# Supply_VCO.net
KiCad netlist of a schematic drawn in Altium Designer
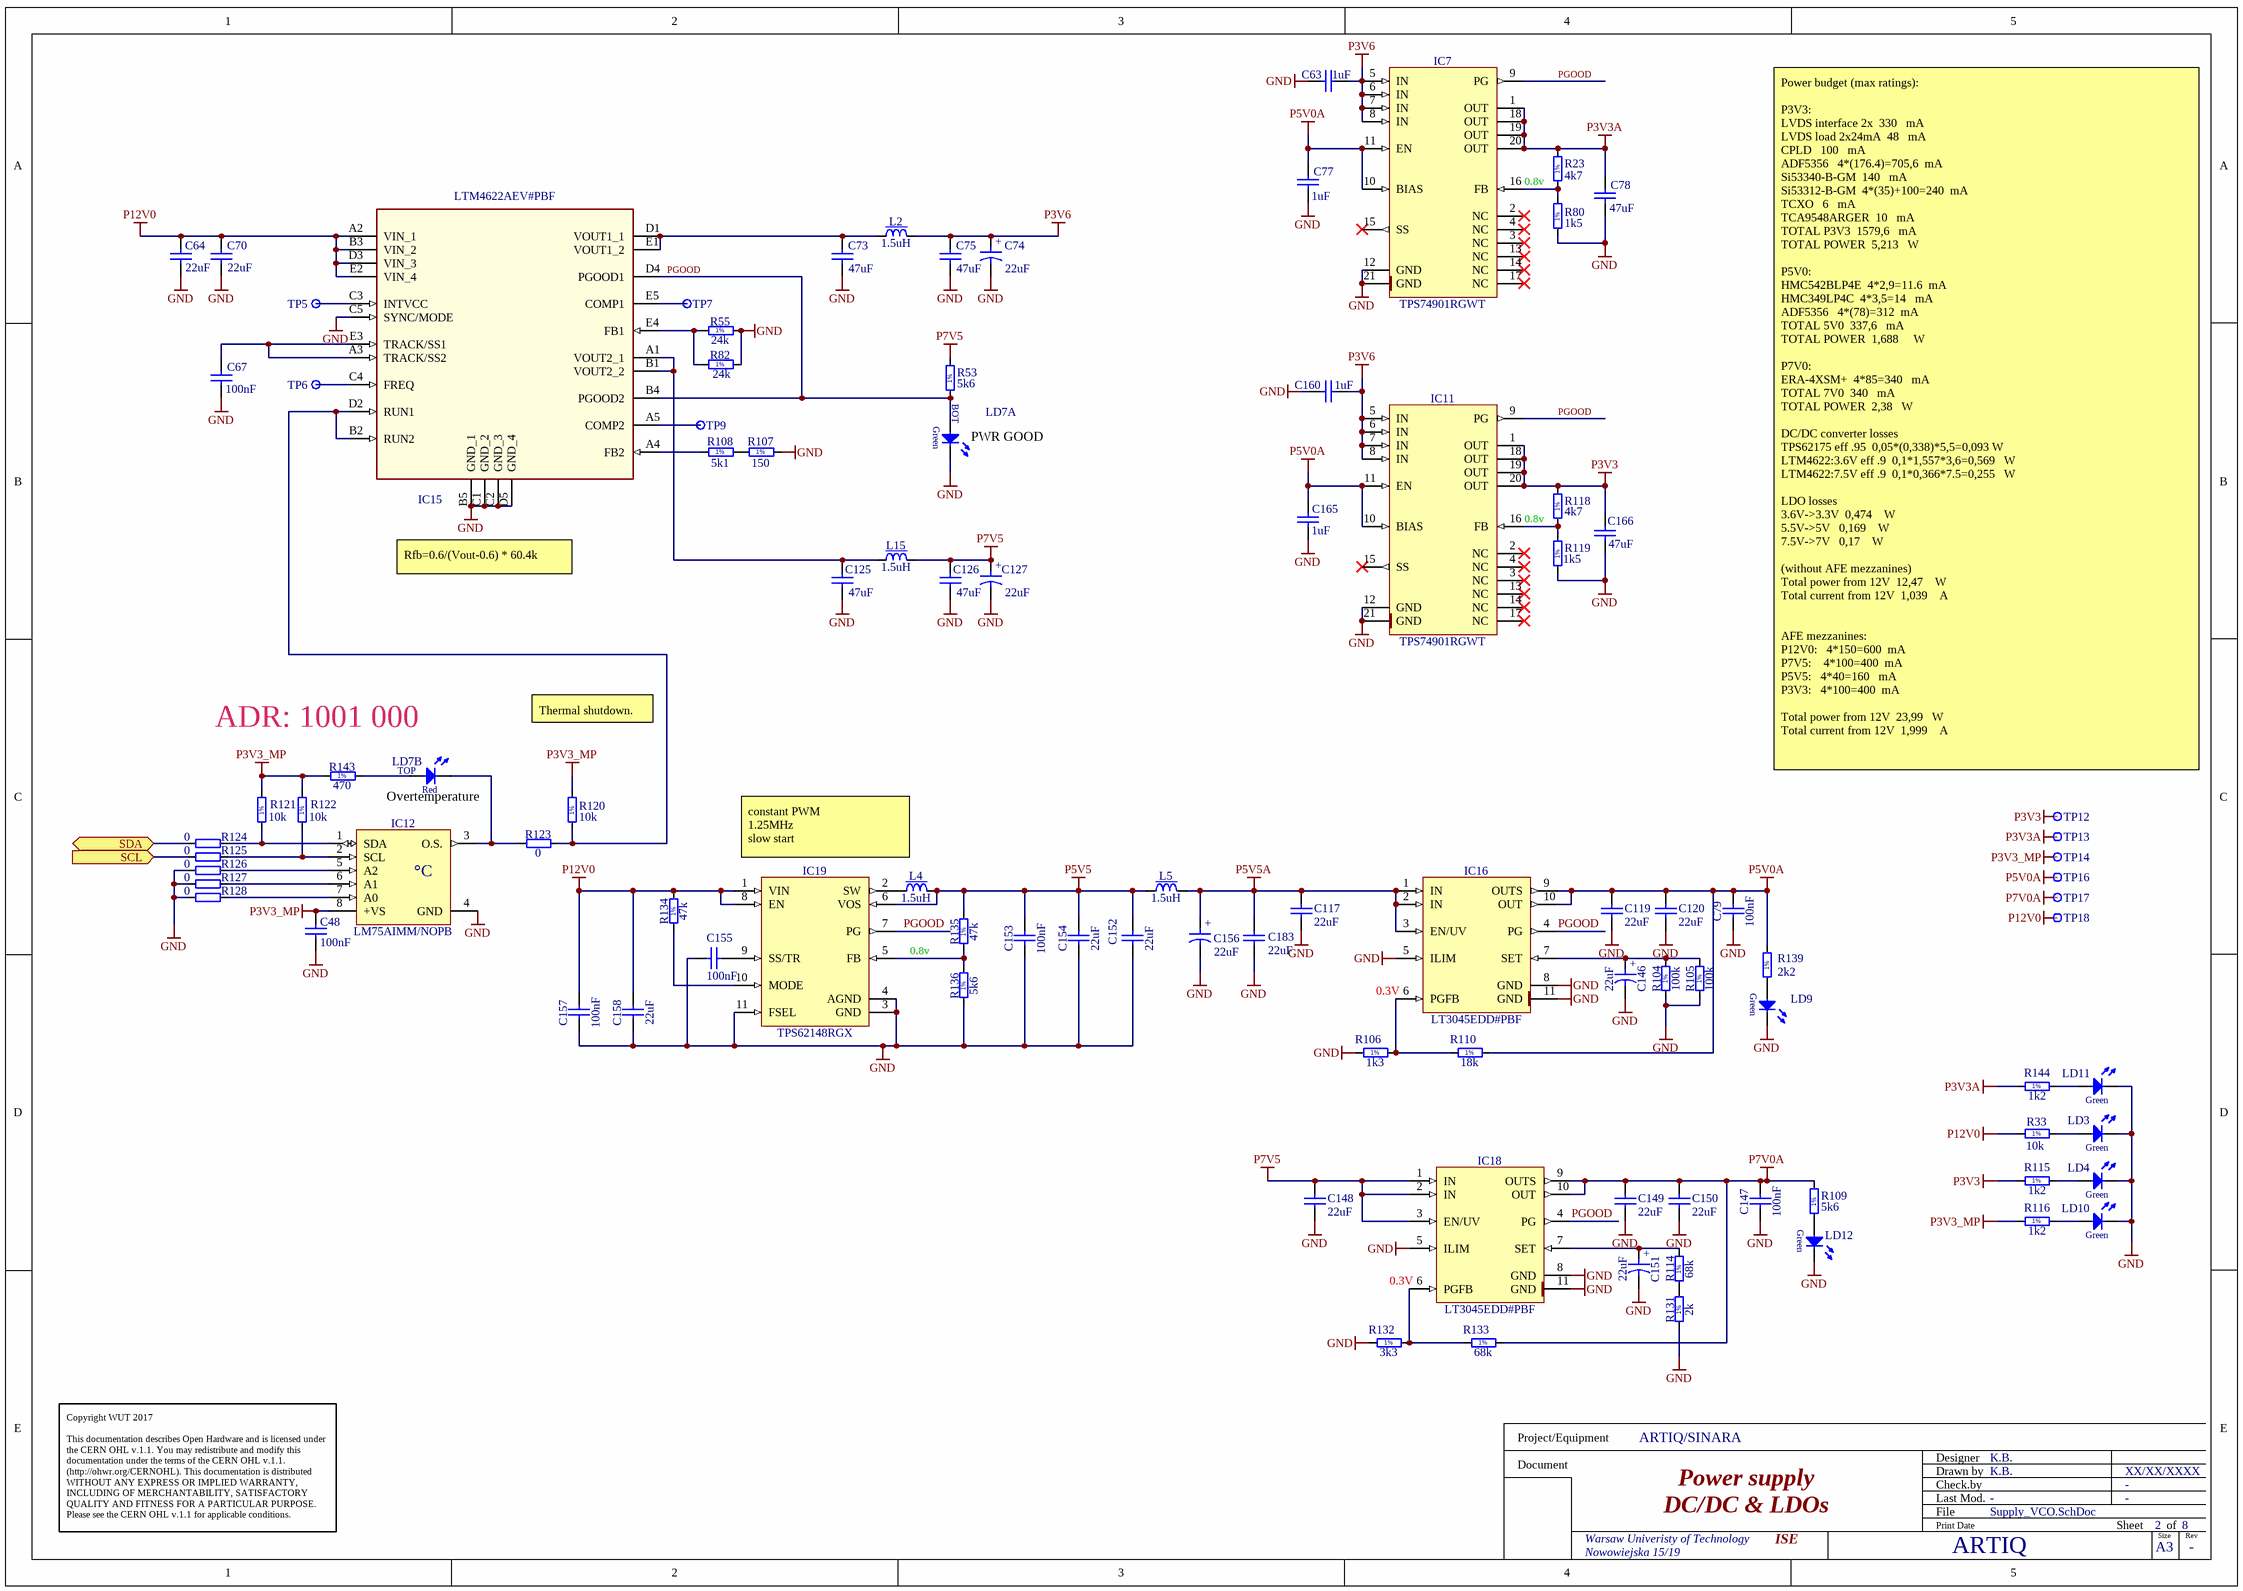
[diagram p0: Supply_VCO.SchDoc]

(export (version "E")
  (design (tool "Eeschema 10.0.6"))
  (components
    (comp (ref "C48")
      (value "100nF")
      (footprint "CAPC1005X55N")
      (description "Non-polarised capacitor")
      (fields (field (name "PART NUMBER") "CC0402_100NF_16V_10%_X5R") (field (name "VOLTAGE") "16V"))
      (libsource (lib "Capacitors") (part "Capacitor - non polarized"))
    )
    (comp (ref "C63")
      (value "1uF")
      (footprint "CAPC1005X55N")
      (description "Non-polarised capacitor")
      (fields (field (name "PART NUMBER") "CC0402_1UF_16V_10%_X5R") (field (name "VOLTAGE") "16V"))
      (libsource (lib "Capacitors") (part "Capacitor - non polarized"))
    )
    (comp (ref "C64")
      (value "22uF")
      (footprint "CAPC2012X135N")
      (description "Non-polarised capacitor")
      (fields (field (name "PART NUMBER") "CC0805_22UF_16V_10%_X5R") (field (name "VOLTAGE") "16V"))
      (libsource (lib "Capacitors") (part "Capacitor - non polarized"))
    )
    (comp (ref "C67")
      (value "100nF")
      (footprint "CAPC1005X55N")
      (description "Non-polarised capacitor")
      (fields (field (name "PART NUMBER") "CC0402_100NF_16V_10%_X5R") (field (name "VOLTAGE") "16V"))
      (libsource (lib "Capacitors") (part "Capacitor - non polarized"))
    )
    (comp (ref "C70")
      (value "22uF")
      (footprint "CAPC2012X135N")
      (description "Non-polarised capacitor")
      (fields (field (name "PART NUMBER") "CC0805_22UF_16V_10%_X5R") (field (name "VOLTAGE") "16V"))
      (libsource (lib "Capacitors") (part "Capacitor - non polarized"))
    )
    (comp (ref "C73")
      (value "47uF")
      (footprint "CAPC3225X270N")
      (description "Non-polarised capacitor")
      (fields (field (name "PART NUMBER") "CC1210_47UF_10V_20%_X5R") (field (name "VOLTAGE") "10V"))
      (libsource (lib "Capacitors") (part "Capacitor - non polarized"))
    )
    (comp (ref "C74")
      (value "22uF")
      (footprint "CAPMP3528X210N")
      (description "Polarised capacitor")
      (fields (field (name "PART NUMBER") "CTE3528-21_22UF_10V_10%_LESR0700") (field (name "VOLTAGE") "10V"))
      (libsource (lib "Capacitors") (part "Capacitor - polarized"))
    )
    (comp (ref "C75")
      (value "47uF")
      (footprint "CAPC3225X270N")
      (description "Non-polarised capacitor")
      (fields (field (name "PART NUMBER") "CC1210_47UF_10V_20%_X5R") (field (name "VOLTAGE") "10V"))
      (libsource (lib "Capacitors") (part "Capacitor - non polarized"))
    )
    (comp (ref "C77")
      (value "1uF")
      (footprint "CAPC1005X55N")
      (description "Non-polarised capacitor")
      (fields (field (name "PART NUMBER") "CC0402_1UF_16V_10%_X5R") (field (name "VOLTAGE") "16V"))
      (libsource (lib "Capacitors") (part "Capacitor - non polarized"))
    )
    (comp (ref "C78")
      (value "47uF")
      (footprint "CAPC3225X270N")
      (description "Non-polarised capacitor")
      (fields (field (name "PART NUMBER") "CC1210_47UF_10V_20%_X5R") (field (name "VOLTAGE") "10V"))
      (libsource (lib "Capacitors") (part "Capacitor - non polarized"))
    )
    (comp (ref "C79")
      (value "100nF")
      (footprint "CAPC1005X55N")
      (description "Non-polarised capacitor")
      (fields (field (name "PART NUMBER") "CC0402_100NF_16V_10%_X5R") (field (name "VOLTAGE") "16V"))
      (libsource (lib "Capacitors") (part "Capacitor - non polarized"))
    )
    (comp (ref "C117")
      (value "22uF")
      (footprint "CAPC2012X135N")
      (description "Non-polarised capacitor")
      (fields (field (name "PART NUMBER") "CC0805_22UF_16V_10%_X5R") (field (name "VOLTAGE") "16V"))
      (libsource (lib "Capacitors") (part "Capacitor - non polarized"))
    )
    (comp (ref "C119")
      (value "22uF")
      (footprint "CAPC2012X135N")
      (description "Non-polarised capacitor")
      (fields (field (name "PART NUMBER") "CC0805_22UF_16V_10%_X5R") (field (name "VOLTAGE") "16V"))
      (libsource (lib "Capacitors") (part "Capacitor - non polarized"))
    )
    (comp (ref "C120")
      (value "22uF")
      (footprint "CAPC2012X135N")
      (description "Non-polarised capacitor")
      (fields (field (name "PART NUMBER") "CC0805_22UF_16V_10%_X5R") (field (name "VOLTAGE") "16V"))
      (libsource (lib "Capacitors") (part "Capacitor - non polarized"))
    )
    (comp (ref "C125")
      (value "47uF")
      (footprint "CAPC3225X270N")
      (description "Non-polarised capacitor")
      (fields (field (name "PART NUMBER") "CC1210_47UF_10V_20%_X5R") (field (name "VOLTAGE") "10V"))
      (libsource (lib "Capacitors") (part "Capacitor - non polarized"))
    )
    (comp (ref "C126")
      (value "47uF")
      (footprint "CAPC3225X270N")
      (description "Non-polarised capacitor")
      (fields (field (name "PART NUMBER") "CC1210_47UF_10V_20%_X5R") (field (name "VOLTAGE") "10V"))
      (libsource (lib "Capacitors") (part "Capacitor - non polarized"))
    )
    (comp (ref "C127")
      (value "22uF")
      (footprint "CAPMP3528X210N")
      (description "Polarised capacitor")
      (fields (field (name "PART NUMBER") "CTE3528-21_22UF_10V_10%_LESR0700") (field (name "VOLTAGE") "10V"))
      (libsource (lib "Capacitors") (part "Capacitor - polarized"))
    )
    (comp (ref "C146")
      (value "22uF")
      (footprint "CAPMP3528X210N")
      (description "Polarised capacitor")
      (fields (field (name "PART NUMBER") "CTE3528-21_22UF_10V_10%_LESR0700") (field (name "VOLTAGE") "10V"))
      (libsource (lib "Capacitors") (part "Capacitor - polarized"))
    )
    (comp (ref "C147")
      (value "100nF")
      (footprint "CAPC1005X55N")
      (description "Non-polarised capacitor")
      (fields (field (name "PART NUMBER") "CC0402_100NF_16V_10%_X5R") (field (name "VOLTAGE") "16V"))
      (libsource (lib "Capacitors") (part "Capacitor - non polarized"))
    )
    (comp (ref "C148")
      (value "22uF")
      (footprint "CAPC2012X135N")
      (description "Non-polarised capacitor")
      (fields (field (name "PART NUMBER") "CC0805_22UF_16V_10%_X5R") (field (name "VOLTAGE") "16V"))
      (libsource (lib "Capacitors") (part "Capacitor - non polarized"))
    )
    (comp (ref "C149")
      (value "22uF")
      (footprint "CAPC2012X135N")
      (description "Non-polarised capacitor")
      (fields (field (name "PART NUMBER") "CC0805_22UF_16V_10%_X5R") (field (name "VOLTAGE") "16V"))
      (libsource (lib "Capacitors") (part "Capacitor - non polarized"))
    )
    (comp (ref "C150")
      (value "22uF")
      (footprint "CAPC2012X135N")
      (description "Non-polarised capacitor")
      (fields (field (name "PART NUMBER") "CC0805_22UF_16V_10%_X5R") (field (name "VOLTAGE") "16V"))
      (libsource (lib "Capacitors") (part "Capacitor - non polarized"))
    )
    (comp (ref "C151")
      (value "22uF")
      (footprint "CAPMP3528X210N")
      (description "Polarised capacitor")
      (fields (field (name "PART NUMBER") "CTE3528-21_22UF_10V_10%_LESR0700") (field (name "VOLTAGE") "10V"))
      (libsource (lib "Capacitors") (part "Capacitor - polarized"))
    )
    (comp (ref "C152")
      (value "22uF")
      (footprint "CAPC2012X135N")
      (description "Non-polarised capacitor")
      (fields (field (name "PART NUMBER") "CC0805_22UF_16V_10%_X5R") (field (name "VOLTAGE") "16V"))
      (libsource (lib "Capacitors") (part "Capacitor - non polarized"))
    )
    (comp (ref "C153")
      (value "100nF")
      (footprint "CAPC1005X55N")
      (description "Non-polarised capacitor")
      (fields (field (name "PART NUMBER") "CC0402_100NF_16V_10%_X5R") (field (name "VOLTAGE") "16V"))
      (libsource (lib "Capacitors") (part "Capacitor - non polarized"))
    )
    (comp (ref "C154")
      (value "22uF")
      (footprint "CAPC2012X135N")
      (description "Non-polarised capacitor")
      (fields (field (name "PART NUMBER") "CC0805_22UF_16V_10%_X5R") (field (name "VOLTAGE") "16V"))
      (libsource (lib "Capacitors") (part "Capacitor - non polarized"))
    )
    (comp (ref "C155")
      (value "100nF")
      (footprint "CAPC1005X55N")
      (description "Non-polarised capacitor")
      (fields (field (name "PART NUMBER") "CC0402_100NF_16V_10%_X5R") (field (name "VOLTAGE") "16V"))
      (libsource (lib "Capacitors") (part "Capacitor - non polarized"))
    )
    (comp (ref "C156")
      (value "22uF")
      (footprint "CAPMP3528X210N")
      (description "Polarised capacitor")
      (fields (field (name "PART NUMBER") "CTE3528-21_22UF_10V_10%_LESR0700") (field (name "VOLTAGE") "10V"))
      (libsource (lib "Capacitors") (part "Capacitor - polarized"))
    )
    (comp (ref "C157")
      (value "100nF")
      (footprint "CAPC1005X55N")
      (description "Non-polarised capacitor")
      (fields (field (name "PART NUMBER") "CC0402_100NF_16V_10%_X5R") (field (name "VOLTAGE") "16V"))
      (libsource (lib "Capacitors") (part "Capacitor - non polarized"))
    )
    (comp (ref "C158")
      (value "22uF")
      (footprint "CAPC2012X135N")
      (description "Non-polarised capacitor")
      (fields (field (name "PART NUMBER") "CC0805_22UF_16V_10%_X5R") (field (name "VOLTAGE") "16V"))
      (libsource (lib "Capacitors") (part "Capacitor - non polarized"))
    )
    (comp (ref "C160")
      (value "1uF")
      (footprint "CAPC1005X55N")
      (description "Non-polarised capacitor")
      (fields (field (name "PART NUMBER") "CC0402_1UF_16V_10%_X5R") (field (name "VOLTAGE") "16V"))
      (libsource (lib "Capacitors") (part "Capacitor - non polarized"))
    )
    (comp (ref "C165")
      (value "1uF")
      (footprint "CAPC1005X55N")
      (description "Non-polarised capacitor")
      (fields (field (name "PART NUMBER") "CC0402_1UF_16V_10%_X5R") (field (name "VOLTAGE") "16V"))
      (libsource (lib "Capacitors") (part "Capacitor - non polarized"))
    )
    (comp (ref "C166")
      (value "47uF")
      (footprint "CAPC3225X270N")
      (description "Non-polarised capacitor")
      (fields (field (name "PART NUMBER") "CC1210_47UF_10V_20%_X5R") (field (name "VOLTAGE") "10V"))
      (libsource (lib "Capacitors") (part "Capacitor - non polarized"))
    )
    (comp (ref "C183")
      (value "22uF")
      (footprint "CAPC2012X135N")
      (description "Non-polarised capacitor")
      (fields (field (name "PART NUMBER") "CC0805_22UF_16V_10%_X5R") (field (name "VOLTAGE") "16V"))
      (libsource (lib "Capacitors") (part "Capacitor - non polarized"))
    )
    (comp (ref "IC7")
      (value "TPS74901RGWT")
      (footprint "QFN65P500X500X100-21N-S325")
      (description "3A, 0.8 to 3.6V Adjustable Low-Dropout Linear Regulator with Programmable Soft-Start")
      (fields (field (name "MANUFACTURER") "TEXAS INSTRUMENTS"))
      (libsource (lib "ICs And Semiconductors") (part "TPS74901RGWT"))
    )
    (comp (ref "IC11")
      (value "TPS74901RGWT")
      (footprint "QFN65P500X500X100-21N-S325")
      (description "3A, 0.8 to 3.6V Adjustable Low-Dropout Linear Regulator with Programmable Soft-Start")
      (fields (field (name "MANUFACTURER") "TEXAS INSTRUMENTS"))
      (libsource (lib "ICs And Semiconductors") (part "TPS74901RGWT"))
    )
    (comp (ref "IC12")
      (value "LM75AIMM/NOPB")
      (footprint "SOP65P490X109-8N")
      (description "Digital Temperature Sensor and Thermal Watchdog with Two-Wire Interface")
      (fields (field (name "MANUFACTURER") "TEXAS INSTRUMENTS"))
      (libsource (lib "ICs And Semiconductors") (part "LM75"))
    )
    (comp (ref "IC15")
      (value "LTM4622AEV#PBF")
      (footprint "LGA25C127P5X5_625X625X190")
      (description "Dual Ultrathin 2A or Single 4A, 3.6V to 20V, 1.5V to 12V   Step-Down DC/DC μModule Regulator")
      (fields (field (name "MANUFACTURER") "LINEAR TECHNOLOGY"))
      (libsource (lib "LIBRARY_SCH") (part "PM_LTM4622"))
    )
    (comp (ref "IC16")
      (value "LT3045EDD#PBF")
      (footprint "SON50P300X300X80-11N-R175X248")
      (description "20V, 500mA, Ultralow Noise, Ultrahigh PSRR Linear Regulator")
      (fields (field (name "MANUFACTURER") "LINEAR TECHNOLOGY"))
      (libsource (lib "ICs And Semiconductors") (part "LT3045EDD"))
    )
    (comp (ref "IC18")
      (value "LT3045EDD#PBF")
      (footprint "SON50P300X300X80-11N-R175X248")
      (description "20V, 500mA, Ultralow Noise, Ultrahigh PSRR Linear Regulator")
      (fields (field (name "MANUFACTURER") "LINEAR TECHNOLOGY"))
      (libsource (lib "ICs And Semiconductors") (part "LT3045EDD"))
    )
    (comp (ref "IC19")
      (value "TPS62148RGX")
      (footprint "TEXAS_RGX0011A")
      (description "3V-17V 2A Step-Down Converter, High Accuracy, With DCS-Control")
      (fields (field (name "MANUFACTURER") "TEXAS INSTRUMENTS"))
      (libsource (lib "ICs And Semiconductors") (part "TPS62148"))
    )
    (comp (ref "L2")
      (value "1.5uH")
      (footprint "IND_TDK_SPM6530")
      (description "Inductor With Core")
      (fields (field (name "PART NUMBER") "IND_1.5UH_20%_TDK_SPM6530") (field (name "POWER") "11A"))
      (libsource (lib "Inductors & Transformers") (part "Inductor With Magnetic core"))
    )
    (comp (ref "L4")
      (value "1.5uH")
      (footprint "IND_TDK_SPM6530")
      (description "Inductor With Core")
      (fields (field (name "PART NUMBER") "IND_1.5UH_20%_TDK_SPM6530") (field (name "POWER") "11A"))
      (libsource (lib "Inductors & Transformers") (part "Inductor With Magnetic core"))
    )
    (comp (ref "L5")
      (value "1.5uH")
      (footprint "IND_TDK_SPM6530")
      (description "Inductor With Core")
      (fields (field (name "PART NUMBER") "IND_1.5UH_20%_TDK_SPM6530") (field (name "POWER") "11A"))
      (libsource (lib "Inductors & Transformers") (part "Inductor With Magnetic core"))
    )
    (comp (ref "L15")
      (value "1.5uH")
      (footprint "IND_TDK_SPM6530")
      (description "Inductor With Core")
      (fields (field (name "PART NUMBER") "IND_1.5UH_20%_TDK_SPM6530") (field (name "POWER") "11A"))
      (libsource (lib "Inductors & Transformers") (part "Inductor With Magnetic core"))
    )
    (comp (ref "LD3")
      (value "Green")
      (footprint "LED_KINGBRIGHT_KPH-1608CGCKr")
      (description "Green 0603")
      (fields
        (field (name "PART NUMBER") "LED_KINGBRIGHT_KPH-1608CGCK")
        (field (name "MANUFACTURER") "KINGBRIGHT")
      )
      (libsource (lib "LIBRARY_SCH") (part "LED_0603_Green"))
    )
    (comp (ref "LD4")
      (value "Green")
      (footprint "LED_KINGBRIGHT_KPH-1608CGCKr")
      (description "Green 0603")
      (fields
        (field (name "PART NUMBER") "LED_KINGBRIGHT_KPH-1608CGCK")
        (field (name "MANUFACTURER") "KINGBRIGHT")
      )
      (libsource (lib "LIBRARY_SCH") (part "LED_0603_Green"))
    )
    (comp (ref "LD7")
      (value "Red/Green")
      (footprint "LED_DIALIGHT_553-0112-200F")
      (description "2x LED  Botom Green, Top Red")
      (fields
        (field (name "PART NUMBER") "LED_DIALIGHT_553-0112-200F")
        (field (name "MANUFACTURER") "DIALIGHT")
      )
      (libsource (lib "ICs And Semiconductors") (part "LED x2 G-1C2A-BOT_R-3C4A-TOP"))
    )
    (comp (ref "LD9")
      (value "Green")
      (footprint "LED_KINGBRIGHT_KPH-1608CGCKr")
      (description "Green 0603")
      (fields
        (field (name "PART NUMBER") "LED_KINGBRIGHT_KPH-1608CGCK")
        (field (name "MANUFACTURER") "KINGBRIGHT")
      )
      (libsource (lib "LIBRARY_SCH") (part "LED_0603_Green"))
    )
    (comp (ref "LD10")
      (value "Green")
      (footprint "LED_KINGBRIGHT_KPH-1608CGCKr")
      (description "Green 0603")
      (fields
        (field (name "PART NUMBER") "LED_KINGBRIGHT_KPH-1608CGCK")
        (field (name "MANUFACTURER") "KINGBRIGHT")
      )
      (libsource (lib "LIBRARY_SCH") (part "LED_0603_Green"))
    )
    (comp (ref "LD11")
      (value "Green")
      (footprint "LED_KINGBRIGHT_KPH-1608CGCKr")
      (description "Green 0603")
      (fields
        (field (name "PART NUMBER") "LED_KINGBRIGHT_KPH-1608CGCK")
        (field (name "MANUFACTURER") "KINGBRIGHT")
      )
      (libsource (lib "LIBRARY_SCH") (part "LED_0603_Green"))
    )
    (comp (ref "LD12")
      (value "Green")
      (footprint "LED_KINGBRIGHT_KPH-1608CGCKr")
      (description "Green 0603")
      (fields
        (field (name "PART NUMBER") "LED_KINGBRIGHT_KPH-1608CGCK")
        (field (name "MANUFACTURER") "KINGBRIGHT")
      )
      (libsource (lib "LIBRARY_SCH") (part "LED_0603_Green"))
    )
    (comp (ref "R23")
      (value "4k7")
      (footprint "RESC1608X55N")
      (description "Resistor - 1%")
      (fields (field (name "PART NUMBER") "R0603_4K7_1%_0.1W_100PPM") (field (name "POWER") "0.1W"))
      (libsource (lib "Resistors") (part "Resistor - 1%"))
    )
    (comp (ref "R33")
      (value "10k")
      (footprint "RESC1005X40N")
      (description "Resistor - 1%")
      (fields (field (name "PART NUMBER") "R0402_10K_1%_0.0625W_100PPM") (field (name "POWER") "0.0625W"))
      (libsource (lib "Resistors") (part "Resistor - 1%"))
    )
    (comp (ref "R53")
      (value "5k6")
      (footprint "RESC1608X55N")
      (description "Resistor - 1%")
      (fields (field (name "PART NUMBER") "R0603_5K6_1%_0.1W_100PPM") (field (name "POWER") "0.1W"))
      (libsource (lib "Resistors") (part "Resistor - 1%"))
    )
    (comp (ref "R55")
      (value "24k")
      (footprint "RESC1608X55N")
      (description "Resistor - 1%")
      (fields (field (name "PART NUMBER") "R0603_24K_1%_0.1W_100PPM") (field (name "POWER") "0.1W"))
      (libsource (lib "Resistors") (part "Resistor - 1%"))
    )
    (comp (ref "R80")
      (value "1k5")
      (footprint "RESC1608X55N")
      (description "Resistor - 1%")
      (fields (field (name "PART NUMBER") "R0603_1K5_1%_0.1W_100PPM") (field (name "POWER") "0.1W"))
      (libsource (lib "Resistors") (part "Resistor - 1%"))
    )
    (comp (ref "R82")
      (value "24k")
      (footprint "RESC1608X55N")
      (description "Resistor - 1%")
      (fields (field (name "PART NUMBER") "R0603_24K_1%_0.1W_100PPM") (field (name "POWER") "0.1W"))
      (libsource (lib "Resistors") (part "Resistor - 1%"))
    )
    (comp (ref "R104")
      (value "100k")
      (footprint "RESC1005X40N")
      (description "Resistor - 1%")
      (fields (field (name "PART NUMBER") "R0402_100K_1%_0.0625W_100PPM") (field (name "POWER") "0.0625W"))
      (libsource (lib "Resistors") (part "Resistor - 1%"))
    )
    (comp (ref "R105")
      (value "100k")
      (footprint "RESC1005X40N")
      (description "Resistor - 1%")
      (fields (field (name "PART NUMBER") "R0402_100K_1%_0.0625W_100PPM") (field (name "POWER") "0.0625W"))
      (libsource (lib "Resistors") (part "Resistor - 1%"))
    )
    (comp (ref "R106")
      (value "1k3")
      (footprint "RESC1608X55N")
      (description "Resistor - 1%")
      (fields (field (name "PART NUMBER") "R0603_1K3_1%_0.1W_100PPM") (field (name "POWER") "0.1W"))
      (libsource (lib "Resistors") (part "Resistor - 1%"))
    )
    (comp (ref "R107")
      (value "150")
      (footprint "RESC1005X40N")
      (description "Resistor - 1%")
      (fields (field (name "PART NUMBER") "R0402_150R_1%_0.0625W_100PPM") (field (name "POWER") "0.0625W"))
      (libsource (lib "Resistors") (part "Resistor - 1%"))
    )
    (comp (ref "R108")
      (value "5k1")
      (footprint "RESC1608X55N")
      (description "Resistor - 1%")
      (fields (field (name "PART NUMBER") "R0603_5K1_1%_0.1W_100PPM") (field (name "POWER") "0.1W"))
      (libsource (lib "Resistors") (part "Resistor - 1%"))
    )
    (comp (ref "R109")
      (value "5k6")
      (footprint "RESC1608X55N")
      (description "Resistor - 1%")
      (fields (field (name "PART NUMBER") "R0603_5K6_1%_0.1W_100PPM") (field (name "POWER") "0.1W"))
      (libsource (lib "Resistors") (part "Resistor - 1%"))
    )
    (comp (ref "R110")
      (value "18k")
      (footprint "RESC1005X40N")
      (description "Resistor - 1%")
      (fields (field (name "PART NUMBER") "R0402_18K_1%_0.0625W_100PPM") (field (name "POWER") "0.0625W"))
      (libsource (lib "Resistors") (part "Resistor - 1%"))
    )
    (comp (ref "R114")
      (value "68k")
      (footprint "RESC1005X40N")
      (description "Resistor - 1%")
      (fields (field (name "PART NUMBER") "R0402_68K_1%_0.0625W_100PPM") (field (name "POWER") "0.0625W"))
      (libsource (lib "Resistors") (part "Resistor - 1%"))
    )
    (comp (ref "R115")
      (value "1k2")
      (footprint "RESC1005X40N")
      (description "Resistor - 1%")
      (fields (field (name "PART NUMBER") "R0402_1K2_1%_0.0625W_100PPM") (field (name "POWER") "0.0625W"))
      (libsource (lib "Resistors") (part "Resistor - 1%"))
    )
    (comp (ref "R116")
      (value "1k2")
      (footprint "RESC1005X40N")
      (description "Resistor - 1%")
      (fields (field (name "PART NUMBER") "R0402_1K2_1%_0.0625W_100PPM") (field (name "POWER") "0.0625W"))
      (libsource (lib "Resistors") (part "Resistor - 1%"))
    )
    (comp (ref "R118")
      (value "4k7")
      (footprint "RESC1608X55N")
      (description "Resistor - 1%")
      (fields (field (name "PART NUMBER") "R0603_4K7_1%_0.1W_100PPM") (field (name "POWER") "0.1W"))
      (libsource (lib "Resistors") (part "Resistor - 1%"))
    )
    (comp (ref "R119")
      (value "1k5")
      (footprint "RESC1608X55N")
      (description "Resistor - 1%")
      (fields (field (name "PART NUMBER") "R0603_1K5_1%_0.1W_100PPM") (field (name "POWER") "0.1W"))
      (libsource (lib "Resistors") (part "Resistor - 1%"))
    )
    (comp (ref "R120")
      (value "10k")
      (footprint "RESC1005X40N")
      (description "Resistor - 1%")
      (fields (field (name "PART NUMBER") "R0402_10K_1%_0.0625W_100PPM") (field (name "POWER") "0.0625W"))
      (libsource (lib "Resistors") (part "Resistor - 1%"))
    )
    (comp (ref "R121")
      (value "10k")
      (footprint "RESC1005X40N")
      (description "Resistor - 1%")
      (fields (field (name "PART NUMBER") "R0402_10K_1%_0.0625W_100PPM") (field (name "POWER") "0.0625W"))
      (libsource (lib "Resistors") (part "Resistor - 1%"))
    )
    (comp (ref "R122")
      (value "10k")
      (footprint "RESC1005X40N")
      (description "Resistor - 1%")
      (fields (field (name "PART NUMBER") "R0402_10K_1%_0.0625W_100PPM") (field (name "POWER") "0.0625W"))
      (libsource (lib "Resistors") (part "Resistor - 1%"))
    )
    (comp (ref "R123")
      (value "0")
      (footprint "RESC1005X40N")
      (description "Resistor")
      (fields (field (name "PART NUMBER") "R0402_0R_JUMPER") (field (name "MANUFACTURER") "GENERIC"))
      (libsource (lib "Resistors") (part "Resistor"))
    )
    (comp (ref "R124")
      (value "0")
      (footprint "RESC1005X40N")
      (description "Resistor")
      (fields (field (name "PART NUMBER") "R0402_0R_JUMPER") (field (name "MANUFACTURER") "GENERIC"))
      (libsource (lib "Resistors") (part "Resistor"))
    )
    (comp (ref "R125")
      (value "0")
      (footprint "RESC1005X40N")
      (description "Resistor")
      (fields (field (name "PART NUMBER") "R0402_0R_JUMPER") (field (name "MANUFACTURER") "GENERIC"))
      (libsource (lib "Resistors") (part "Resistor"))
    )
    (comp (ref "R126")
      (value "0")
      (footprint "RESC1005X40N")
      (description "Resistor")
      (fields (field (name "PART NUMBER") "R0402_0R_JUMPER") (field (name "MANUFACTURER") "GENERIC"))
      (libsource (lib "Resistors") (part "Resistor"))
    )
    (comp (ref "R127")
      (value "0")
      (footprint "RESC1005X40N")
      (description "Resistor")
      (fields (field (name "PART NUMBER") "R0402_0R_JUMPER") (field (name "MANUFACTURER") "GENERIC"))
      (libsource (lib "Resistors") (part "Resistor"))
    )
    (comp (ref "R128")
      (value "0")
      (footprint "RESC1005X40N")
      (description "Resistor")
      (fields (field (name "PART NUMBER") "R0402_0R_JUMPER") (field (name "MANUFACTURER") "GENERIC"))
      (libsource (lib "Resistors") (part "Resistor"))
    )
    (comp (ref "R131")
      (value "2k")
      (footprint "RESC1005X40N")
      (description "Resistor - 1%")
      (fields (field (name "PART NUMBER") "R0402_2K_1%_0.0625W_100PPM") (field (name "POWER") "0.0625W"))
      (libsource (lib "Resistors") (part "Resistor - 1%"))
    )
    (comp (ref "R132")
      (value "3k3")
      (footprint "RESC1608X55N")
      (description "Resistor - 1%")
      (fields (field (name "PART NUMBER") "R0603_3K3_1%_0.1W_100PPM") (field (name "POWER") "0.1W"))
      (libsource (lib "Resistors") (part "Resistor - 1%"))
    )
    (comp (ref "R133")
      (value "68k")
      (footprint "RESC1005X40N")
      (description "Resistor - 1%")
      (fields (field (name "PART NUMBER") "R0402_68K_1%_0.0625W_100PPM") (field (name "POWER") "0.0625W"))
      (libsource (lib "Resistors") (part "Resistor - 1%"))
    )
    (comp (ref "R134")
      (value "47k")
      (footprint "RESC1005X40N")
      (description "Resistor - 1%")
      (fields (field (name "PART NUMBER") "R0402_47K_1%_0.0625W_100PPM") (field (name "POWER") "0.0625W"))
      (libsource (lib "Resistors") (part "Resistor - 1%"))
    )
    (comp (ref "R135")
      (value "47k")
      (footprint "RESC1005X40N")
      (description "Resistor - 1%")
      (fields (field (name "PART NUMBER") "R0402_47K_1%_0.0625W_100PPM") (field (name "POWER") "0.0625W"))
      (libsource (lib "Resistors") (part "Resistor - 1%"))
    )
    (comp (ref "R136")
      (value "5k6")
      (footprint "RESC1005X40N")
      (description "Resistor - 1%")
      (fields (field (name "PART NUMBER") "R0402_5K6_1%_0.0625W_100PPM") (field (name "POWER") "0.0625W"))
      (libsource (lib "Resistors") (part "Resistor - 1%"))
    )
    (comp (ref "R139")
      (value "2k2")
      (footprint "RESC1608X55N")
      (description "Resistor - 1%")
      (fields (field (name "PART NUMBER") "R0603_2K2_1%_0.1W_100PPM") (field (name "POWER") "0.1W"))
      (libsource (lib "Resistors") (part "Resistor - 1%"))
    )
    (comp (ref "R143")
      (value "470")
      (footprint "RESC1005X40N")
      (description "Resistor - 1%")
      (fields (field (name "PART NUMBER") "R0402_470R_1%_0.0625W_100PPM") (field (name "POWER") "0.0625W"))
      (libsource (lib "Resistors") (part "Resistor - 1%"))
    )
    (comp (ref "R144")
      (value "1k2")
      (footprint "RESC1005X40N")
      (description "Resistor - 1%")
      (fields (field (name "PART NUMBER") "R0402_1K2_1%_0.0625W_100PPM") (field (name "POWER") "0.0625W"))
      (libsource (lib "Resistors") (part "Resistor - 1%"))
    )
    (comp (ref "TP5")
      (value "Test Point")
      (footprint "TPS127")
      (fields (field (name "PART NUMBER") "SMD_PAD_1.27X1.27MM"))
      (libsource (lib "Eletro-mechanical") (part "Test Point"))
    )
    (comp (ref "TP6")
      (value "Test Point")
      (footprint "TPS127")
      (fields (field (name "PART NUMBER") "SMD_PAD_1.27X1.27MM"))
      (libsource (lib "Eletro-mechanical") (part "Test Point"))
    )
    (comp (ref "TP7")
      (value "Test Point")
      (footprint "TPS127")
      (fields (field (name "PART NUMBER") "SMD_PAD_1.27X1.27MM"))
      (libsource (lib "Eletro-mechanical") (part "Test Point"))
    )
    (comp (ref "TP9")
      (value "Test Point")
      (footprint "TPS127")
      (fields (field (name "PART NUMBER") "SMD_PAD_1.27X1.27MM"))
      (libsource (lib "Eletro-mechanical") (part "Test Point"))
    )
    (comp (ref "TP12")
      (value "Test Point")
      (footprint "TPS127")
      (fields (field (name "PART NUMBER") "SMD_PAD_1.27X1.27MM"))
      (libsource (lib "Eletro-mechanical") (part "Test Point"))
    )
    (comp (ref "TP13")
      (value "Test Point")
      (footprint "TPS127")
      (fields (field (name "PART NUMBER") "SMD_PAD_1.27X1.27MM"))
      (libsource (lib "Eletro-mechanical") (part "Test Point"))
    )
    (comp (ref "TP14")
      (value "Test Point")
      (footprint "TPS127")
      (fields (field (name "PART NUMBER") "SMD_PAD_1.27X1.27MM"))
      (libsource (lib "Eletro-mechanical") (part "Test Point"))
    )
    (comp (ref "TP16")
      (value "Test Point")
      (footprint "TPS127")
      (fields (field (name "PART NUMBER") "SMD_PAD_1.27X1.27MM"))
      (libsource (lib "Eletro-mechanical") (part "Test Point"))
    )
    (comp (ref "TP17")
      (value "Test Point")
      (footprint "TPS127")
      (fields (field (name "PART NUMBER") "SMD_PAD_1.27X1.27MM"))
      (libsource (lib "Eletro-mechanical") (part "Test Point"))
    )
    (comp (ref "TP18")
      (value "Test Point")
      (footprint "TPS127")
      (fields (field (name "PART NUMBER") "SMD_PAD_1.27X1.27MM"))
      (libsource (lib "Eletro-mechanical") (part "Test Point"))
    )
  )
  (nets
    (net (code "1") (name "/PGOOD") (class "Default")
      (node (ref "IC11") (pin "9") (pinfunction "PG_9") (pintype "output"))
      (node (ref "IC15") (pin "B4") (pinfunction "PGOOD2_B4") (pintype "open_collector"))
      (node (ref "IC15") (pin "D4") (pinfunction "PGOOD1_D4") (pintype "open_collector"))
      (node (ref "IC16") (pin "4") (pinfunction "PG_4") (pintype "output"))
      (node (ref "IC18") (pin "4") (pinfunction "PG_4") (pintype "output"))
      (node (ref "IC19") (pin "7") (pinfunction "PG_7") (pintype "output"))
      (node (ref "IC7") (pin "9") (pinfunction "PG_9") (pintype "output"))
      (node (ref "LD7") (pin "2") (pinfunction "A_2") (pintype "passive"))
      (node (ref "R53") (pin "1") (pinfunction "1_1") (pintype "passive"))
    )
    (net (code "2") (name "/SCL") (class "Default")
      (node (ref "R125") (pin "1") (pinfunction "1_1") (pintype "passive"))
    )
    (net (code "3") (name "/SDA") (class "Default")
      (node (ref "R124") (pin "1") (pinfunction "1_1") (pintype "passive"))
    )
    (net (code "4") (name "GND") (class "Default")
      (node (ref "C117") (pin "2") (pinfunction "2_2") (pintype "passive"))
      (node (ref "C119") (pin "2") (pinfunction "2_2") (pintype "passive"))
      (node (ref "C120") (pin "2") (pinfunction "2_2") (pintype "passive"))
      (node (ref "C125") (pin "1") (pinfunction "1_1") (pintype "passive"))
      (node (ref "C126") (pin "1") (pinfunction "1_1") (pintype "passive"))
      (node (ref "C127") (pin "2") (pinfunction "2_2") (pintype "passive"))
      (node (ref "C146") (pin "2") (pinfunction "2_2") (pintype "passive"))
      (node (ref "C147") (pin "1") (pinfunction "1_1") (pintype "passive"))
      (node (ref "C148") (pin "2") (pinfunction "2_2") (pintype "passive"))
      (node (ref "C149") (pin "2") (pinfunction "2_2") (pintype "passive"))
      (node (ref "C150") (pin "2") (pinfunction "2_2") (pintype "passive"))
      (node (ref "C151") (pin "2") (pinfunction "2_2") (pintype "passive"))
      (node (ref "C152") (pin "1") (pinfunction "1_1") (pintype "passive"))
      (node (ref "C153") (pin "1") (pinfunction "1_1") (pintype "passive"))
      (node (ref "C154") (pin "1") (pinfunction "1_1") (pintype "passive"))
      (node (ref "C155") (pin "2") (pinfunction "2_2") (pintype "passive"))
      (node (ref "C156") (pin "2") (pinfunction "2_2") (pintype "passive"))
      (node (ref "C157") (pin "1") (pinfunction "1_1") (pintype "passive"))
      (node (ref "C158") (pin "1") (pinfunction "1_1") (pintype "passive"))
      (node (ref "C160") (pin "2") (pinfunction "2_2") (pintype "passive"))
      (node (ref "C165") (pin "1") (pinfunction "1_1") (pintype "passive"))
      (node (ref "C166") (pin "1") (pinfunction "1_1") (pintype "passive"))
      (node (ref "C183") (pin "1") (pinfunction "1_1") (pintype "passive"))
      (node (ref "C48") (pin "1") (pinfunction "1_1") (pintype "passive"))
      (node (ref "C63") (pin "2") (pinfunction "2_2") (pintype "passive"))
      (node (ref "C64") (pin "1") (pinfunction "1_1") (pintype "passive"))
      (node (ref "C67") (pin "1") (pinfunction "1_1") (pintype "passive"))
      (node (ref "C70") (pin "1") (pinfunction "1_1") (pintype "passive"))
      (node (ref "C73") (pin "1") (pinfunction "1_1") (pintype "passive"))
      (node (ref "C74") (pin "2") (pinfunction "2_2") (pintype "passive"))
      (node (ref "C75") (pin "1") (pinfunction "1_1") (pintype "passive"))
      (node (ref "C77") (pin "1") (pinfunction "1_1") (pintype "passive"))
      (node (ref "C78") (pin "1") (pinfunction "1_1") (pintype "passive"))
      (node (ref "C79") (pin "1") (pinfunction "1_1") (pintype "passive"))
      (node (ref "IC11") (pin "12") (pinfunction "GND_12") (pintype "power_in"))
      (node (ref "IC11") (pin "21") (pinfunction "GND_21") (pintype "power_in"))
      (node (ref "IC12") (pin "4") (pinfunction "GND_4") (pintype "power_in"))
      (node (ref "IC15") (pin "B5") (pinfunction "GND_1_B5") (pintype "power_in"))
      (node (ref "IC15") (pin "C1") (pinfunction "GND_2_C1") (pintype "power_in"))
      (node (ref "IC15") (pin "C2") (pinfunction "GND_3_C2") (pintype "power_in"))
      (node (ref "IC15") (pin "C5") (pinfunction "SYNC/MODE_C5") (pintype "input"))
      (node (ref "IC15") (pin "D5") (pinfunction "GND_4_D5") (pintype "power_in"))
      (node (ref "IC16") (pin "11") (pinfunction "GND_11") (pintype "power_in"))
      (node (ref "IC16") (pin "5") (pinfunction "ILIM_5") (pintype "input"))
      (node (ref "IC16") (pin "8") (pinfunction "GND_8") (pintype "power_in"))
      (node (ref "IC18") (pin "11") (pinfunction "GND_11") (pintype "power_in"))
      (node (ref "IC18") (pin "5") (pinfunction "ILIM_5") (pintype "input"))
      (node (ref "IC18") (pin "8") (pinfunction "GND_8") (pintype "power_in"))
      (node (ref "IC19") (pin "11") (pinfunction "FSEL_11") (pintype "input"))
      (node (ref "IC19") (pin "3") (pinfunction "GND_3") (pintype "power_in"))
      (node (ref "IC19") (pin "4") (pinfunction "AGND_4") (pintype "power_in"))
      (node (ref "IC7") (pin "12") (pinfunction "GND_12") (pintype "power_in"))
      (node (ref "IC7") (pin "21") (pinfunction "GND_21") (pintype "power_in"))
      (node (ref "LD10") (pin "1") (pinfunction "C_1") (pintype "passive"))
      (node (ref "LD11") (pin "1") (pinfunction "C_1") (pintype "passive"))
      (node (ref "LD12") (pin "1") (pinfunction "C_1") (pintype "passive"))
      (node (ref "LD3") (pin "1") (pinfunction "C_1") (pintype "passive"))
      (node (ref "LD4") (pin "1") (pinfunction "C_1") (pintype "passive"))
      (node (ref "LD7") (pin "1") (pinfunction "C_1") (pintype "passive"))
      (node (ref "LD9") (pin "1") (pinfunction "C_1") (pintype "passive"))
      (node (ref "R104") (pin "1") (pinfunction "1_1") (pintype "passive"))
      (node (ref "R105") (pin "1") (pinfunction "1_1") (pintype "passive"))
      (node (ref "R106") (pin "1") (pinfunction "1_1") (pintype "passive"))
      (node (ref "R107") (pin "2") (pinfunction "2_2") (pintype "passive"))
      (node (ref "R119") (pin "1") (pinfunction "1_1") (pintype "passive"))
      (node (ref "R126") (pin "1") (pinfunction "1_1") (pintype "passive"))
      (node (ref "R127") (pin "1") (pinfunction "1_1") (pintype "passive"))
      (node (ref "R128") (pin "1") (pinfunction "1_1") (pintype "passive"))
      (node (ref "R131") (pin "1") (pinfunction "1_1") (pintype "passive"))
      (node (ref "R132") (pin "1") (pinfunction "1_1") (pintype "passive"))
      (node (ref "R136") (pin "1") (pinfunction "1_1") (pintype "passive"))
      (node (ref "R55") (pin "2") (pinfunction "2_2") (pintype "passive"))
      (node (ref "R80") (pin "1") (pinfunction "1_1") (pintype "passive"))
      (node (ref "R82") (pin "2") (pinfunction "2_2") (pintype "passive"))
    )
    (net (code "5") (name "Net-(IC7-FB)") (class "Default")
      (node (ref "IC7") (pin "16") (pinfunction "FB_16") (pintype "input"))
      (node (ref "R23") (pin "1") (pinfunction "1_1") (pintype "passive"))
      (node (ref "R80") (pin "2") (pinfunction "2_2") (pintype "passive"))
    )
    (net (code "6") (name "Net-(IC11-FB)") (class "Default")
      (node (ref "IC11") (pin "16") (pinfunction "FB_16") (pintype "input"))
      (node (ref "R118") (pin "1") (pinfunction "1_1") (pintype "passive"))
      (node (ref "R119") (pin "2") (pinfunction "2_2") (pintype "passive"))
    )
    (net (code "7") (name "Net-(IC12-A0)") (class "Default")
      (node (ref "IC12") (pin "7") (pinfunction "A0_7") (pintype "input"))
      (node (ref "R128") (pin "2") (pinfunction "2_2") (pintype "passive"))
    )
    (net (code "8") (name "Net-(IC12-A1)") (class "Default")
      (node (ref "IC12") (pin "6") (pinfunction "A1_6") (pintype "input"))
      (node (ref "R127") (pin "2") (pinfunction "2_2") (pintype "passive"))
    )
    (net (code "9") (name "Net-(IC12-A2)") (class "Default")
      (node (ref "IC12") (pin "5") (pinfunction "A2_5") (pintype "input"))
      (node (ref "R126") (pin "2") (pinfunction "2_2") (pintype "passive"))
    )
    (net (code "10") (name "Net-(IC12-O.S.)") (class "Default")
      (node (ref "IC12") (pin "3") (pinfunction "O.S._3") (pintype "output"))
      (node (ref "LD7") (pin "3") (pinfunction "C_3") (pintype "passive"))
      (node (ref "R123") (pin "1") (pinfunction "1_1") (pintype "passive"))
    )
    (net (code "11") (name "Net-(IC12-SCL)") (class "Default")
      (node (ref "IC12") (pin "2") (pinfunction "SCL_2") (pintype "input"))
      (node (ref "R122") (pin "1") (pinfunction "1_1") (pintype "passive"))
      (node (ref "R125") (pin "2") (pinfunction "2_2") (pintype "passive"))
    )
    (net (code "12") (name "Net-(IC12-SDA)") (class "Default")
      (node (ref "IC12") (pin "1") (pinfunction "SDA_1") (pintype "bidirectional"))
      (node (ref "R121") (pin "1") (pinfunction "1_1") (pintype "passive"))
      (node (ref "R124") (pin "2") (pinfunction "2_2") (pintype "passive"))
    )
    (net (code "13") (name "Net-(IC15-COMP1)") (class "Default")
      (node (ref "IC15") (pin "E5") (pinfunction "COMP1_E5") (pintype "passive"))
      (node (ref "TP7") (pin "1") (pinfunction "1_1") (pintype "bidirectional"))
    )
    (net (code "14") (name "Net-(IC15-COMP2)") (class "Default")
      (node (ref "IC15") (pin "A5") (pinfunction "COMP2_A5") (pintype "passive"))
      (node (ref "TP9") (pin "1") (pinfunction "1_1") (pintype "bidirectional"))
    )
    (net (code "15") (name "Net-(IC15-FB1)") (class "Default")
      (node (ref "IC15") (pin "E4") (pinfunction "FB1_E4") (pintype "input"))
      (node (ref "R55") (pin "1") (pinfunction "1_1") (pintype "passive"))
      (node (ref "R82") (pin "1") (pinfunction "1_1") (pintype "passive"))
    )
    (net (code "16") (name "Net-(IC15-FB2)") (class "Default")
      (node (ref "IC15") (pin "A4") (pinfunction "FB2_A4") (pintype "input"))
      (node (ref "R108") (pin "1") (pinfunction "1_1") (pintype "passive"))
    )
    (net (code "17") (name "Net-(IC15-FREQ)") (class "Default")
      (node (ref "IC15") (pin "C4") (pinfunction "FREQ_C4") (pintype "input"))
      (node (ref "TP6") (pin "1") (pinfunction "1_1") (pintype "bidirectional"))
    )
    (net (code "18") (name "Net-(IC15-INTVCC)") (class "Default")
      (node (ref "IC15") (pin "C3") (pinfunction "INTVCC_C3") (pintype "input"))
      (node (ref "TP5") (pin "1") (pinfunction "1_1") (pintype "bidirectional"))
    )
    (net (code "19") (name "Net-(IC15-RUN1)") (class "Default")
      (node (ref "IC15") (pin "B2") (pinfunction "RUN2_B2") (pintype "input"))
      (node (ref "IC15") (pin "D2") (pinfunction "RUN1_D2") (pintype "input"))
      (node (ref "R120") (pin "1") (pinfunction "1_1") (pintype "passive"))
      (node (ref "R123") (pin "2") (pinfunction "2_2") (pintype "passive"))
    )
    (net (code "20") (name "Net-(IC15-TRACK{slash}SS1)") (class "Default")
      (node (ref "C67") (pin "2") (pinfunction "2_2") (pintype "passive"))
      (node (ref "IC15") (pin "A3") (pinfunction "TRACK/SS2_A3") (pintype "input"))
      (node (ref "IC15") (pin "E3") (pinfunction "TRACK/SS1_E3") (pintype "input"))
    )
    (net (code "21") (name "Net-(IC15-VOUT1_1)") (class "Default")
      (node (ref "C73") (pin "2") (pinfunction "2_2") (pintype "passive"))
      (node (ref "IC15") (pin "D1") (pinfunction "VOUT1_1_D1") (pintype "power_in"))
      (node (ref "IC15") (pin "E1") (pinfunction "VOUT1_2_E1") (pintype "power_in"))
      (node (ref "L2") (pin "1") (pinfunction "1_1") (pintype "passive"))
    )
    (net (code "22") (name "Net-(IC15-VOUT2_1)") (class "Default")
      (node (ref "C125") (pin "2") (pinfunction "2_2") (pintype "passive"))
      (node (ref "IC15") (pin "A1") (pinfunction "VOUT2_1_A1") (pintype "power_in"))
      (node (ref "IC15") (pin "B1") (pinfunction "VOUT2_2_B1") (pintype "power_in"))
      (node (ref "L15") (pin "1") (pinfunction "1_1") (pintype "passive"))
    )
    (net (code "23") (name "Net-(IC16-PGFB)") (class "Default")
      (node (ref "IC16") (pin "6") (pinfunction "PGFB_6") (pintype "input"))
      (node (ref "R106") (pin "2") (pinfunction "2_2") (pintype "passive"))
      (node (ref "R110") (pin "1") (pinfunction "1_1") (pintype "passive"))
    )
    (net (code "24") (name "Net-(IC16-SET)") (class "Default")
      (node (ref "C146") (pin "1") (pinfunction "1_1") (pintype "passive"))
      (node (ref "IC16") (pin "7") (pinfunction "SET_7") (pintype "input"))
      (node (ref "R104") (pin "2") (pinfunction "2_2") (pintype "passive"))
      (node (ref "R105") (pin "2") (pinfunction "2_2") (pintype "passive"))
    )
    (net (code "25") (name "Net-(IC18-PGFB)") (class "Default")
      (node (ref "IC18") (pin "6") (pinfunction "PGFB_6") (pintype "input"))
      (node (ref "R132") (pin "2") (pinfunction "2_2") (pintype "passive"))
      (node (ref "R133") (pin "1") (pinfunction "1_1") (pintype "passive"))
    )
    (net (code "26") (name "Net-(IC18-SET)") (class "Default")
      (node (ref "C151") (pin "1") (pinfunction "1_1") (pintype "passive"))
      (node (ref "IC18") (pin "7") (pinfunction "SET_7") (pintype "input"))
      (node (ref "R114") (pin "2") (pinfunction "2_2") (pintype "passive"))
    )
    (net (code "27") (name "Net-(IC19-FB)") (class "Default")
      (node (ref "IC19") (pin "5") (pinfunction "FB_5") (pintype "input"))
      (node (ref "R135") (pin "1") (pinfunction "1_1") (pintype "passive"))
      (node (ref "R136") (pin "2") (pinfunction "2_2") (pintype "passive"))
    )
    (net (code "28") (name "Net-(IC19-MODE)") (class "Default")
      (node (ref "IC19") (pin "10") (pinfunction "MODE_10") (pintype "input"))
      (node (ref "R134") (pin "1") (pinfunction "1_1") (pintype "passive"))
    )
    (net (code "29") (name "Net-(IC19-SS{slash}TR)") (class "Default")
      (node (ref "C155") (pin "1") (pinfunction "1_1") (pintype "passive"))
      (node (ref "IC19") (pin "9") (pinfunction "SS/TR_9") (pintype "input"))
    )
    (net (code "30") (name "Net-(IC19-SW)") (class "Default")
      (node (ref "IC19") (pin "2") (pinfunction "SW_2") (pintype "output"))
      (node (ref "L4") (pin "1") (pinfunction "1_1") (pintype "passive"))
    )
    (net (code "31") (name "Net-(LD3-A)") (class "Default")
      (node (ref "LD3") (pin "2") (pinfunction "A_2") (pintype "passive"))
      (node (ref "R33") (pin "2") (pinfunction "2_2") (pintype "passive"))
    )
    (net (code "32") (name "Net-(LD4-A)") (class "Default")
      (node (ref "LD4") (pin "2") (pinfunction "A_2") (pintype "passive"))
      (node (ref "R115") (pin "2") (pinfunction "2_2") (pintype "passive"))
    )
    (net (code "33") (name "Net-(LD7B-A)") (class "Default")
      (node (ref "LD7") (pin "4") (pinfunction "A_4") (pintype "passive"))
      (node (ref "R143") (pin "2") (pinfunction "2_2") (pintype "passive"))
    )
    (net (code "34") (name "Net-(LD9-A)") (class "Default")
      (node (ref "LD9") (pin "2") (pinfunction "A_2") (pintype "passive"))
      (node (ref "R139") (pin "1") (pinfunction "1_1") (pintype "passive"))
    )
    (net (code "35") (name "Net-(LD10-A)") (class "Default")
      (node (ref "LD10") (pin "2") (pinfunction "A_2") (pintype "passive"))
      (node (ref "R116") (pin "2") (pinfunction "2_2") (pintype "passive"))
    )
    (net (code "36") (name "Net-(LD11-A)") (class "Default")
      (node (ref "LD11") (pin "2") (pinfunction "A_2") (pintype "passive"))
      (node (ref "R144") (pin "2") (pinfunction "2_2") (pintype "passive"))
    )
    (net (code "37") (name "Net-(LD12-A)") (class "Default")
      (node (ref "LD12") (pin "2") (pinfunction "A_2") (pintype "passive"))
      (node (ref "R109") (pin "1") (pinfunction "1_1") (pintype "passive"))
    )
    (net (code "38") (name "Net-(R107-Pad1)") (class "Default")
      (node (ref "R107") (pin "1") (pinfunction "1_1") (pintype "passive"))
      (node (ref "R108") (pin "2") (pinfunction "2_2") (pintype "passive"))
    )
    (net (code "39") (name "Net-(R114-Pad1)") (class "Default")
      (node (ref "R114") (pin "1") (pinfunction "1_1") (pintype "passive"))
      (node (ref "R131") (pin "2") (pinfunction "2_2") (pintype "passive"))
    )
    (net (code "40") (name "P3V3") (class "Default")
      (node (ref "C166") (pin "2") (pinfunction "2_2") (pintype "passive"))
      (node (ref "IC11") (pin "1") (pinfunction "OUT_1") (pintype "power_in"))
      (node (ref "IC11") (pin "18") (pinfunction "OUT_18") (pintype "power_in"))
      (node (ref "IC11") (pin "19") (pinfunction "OUT_19") (pintype "power_in"))
      (node (ref "IC11") (pin "20") (pinfunction "OUT_20") (pintype "power_in"))
      (node (ref "R115") (pin "1") (pinfunction "1_1") (pintype "passive"))
      (node (ref "R118") (pin "2") (pinfunction "2_2") (pintype "passive"))
      (node (ref "TP12") (pin "1") (pinfunction "1_1") (pintype "bidirectional"))
    )
    (net (code "41") (name "P3V3A") (class "Default")
      (node (ref "C78") (pin "2") (pinfunction "2_2") (pintype "passive"))
      (node (ref "IC7") (pin "1") (pinfunction "OUT_1") (pintype "power_in"))
      (node (ref "IC7") (pin "18") (pinfunction "OUT_18") (pintype "power_in"))
      (node (ref "IC7") (pin "19") (pinfunction "OUT_19") (pintype "power_in"))
      (node (ref "IC7") (pin "20") (pinfunction "OUT_20") (pintype "power_in"))
      (node (ref "R144") (pin "1") (pinfunction "1_1") (pintype "passive"))
      (node (ref "R23") (pin "2") (pinfunction "2_2") (pintype "passive"))
      (node (ref "TP13") (pin "1") (pinfunction "1_1") (pintype "bidirectional"))
    )
    (net (code "42") (name "P3V3_MP") (class "Default")
      (node (ref "C48") (pin "2") (pinfunction "2_2") (pintype "passive"))
      (node (ref "IC12") (pin "8") (pinfunction "+VS_8") (pintype "power_in"))
      (node (ref "R116") (pin "1") (pinfunction "1_1") (pintype "passive"))
      (node (ref "R120") (pin "2") (pinfunction "2_2") (pintype "passive"))
      (node (ref "R121") (pin "2") (pinfunction "2_2") (pintype "passive"))
      (node (ref "R122") (pin "2") (pinfunction "2_2") (pintype "passive"))
      (node (ref "R143") (pin "1") (pinfunction "1_1") (pintype "passive"))
      (node (ref "TP14") (pin "1") (pinfunction "1_1") (pintype "bidirectional"))
    )
    (net (code "43") (name "P3V6") (class "Default")
      (node (ref "C160") (pin "1") (pinfunction "1_1") (pintype "passive"))
      (node (ref "C63") (pin "1") (pinfunction "1_1") (pintype "passive"))
      (node (ref "C74") (pin "1") (pinfunction "1_1") (pintype "passive"))
      (node (ref "C75") (pin "2") (pinfunction "2_2") (pintype "passive"))
      (node (ref "IC11") (pin "5") (pinfunction "IN_5") (pintype "input"))
      (node (ref "IC11") (pin "6") (pinfunction "IN_6") (pintype "input"))
      (node (ref "IC11") (pin "7") (pinfunction "IN_7") (pintype "input"))
      (node (ref "IC11") (pin "8") (pinfunction "IN_8") (pintype "input"))
      (node (ref "IC7") (pin "5") (pinfunction "IN_5") (pintype "input"))
      (node (ref "IC7") (pin "6") (pinfunction "IN_6") (pintype "input"))
      (node (ref "IC7") (pin "7") (pinfunction "IN_7") (pintype "input"))
      (node (ref "IC7") (pin "8") (pinfunction "IN_8") (pintype "input"))
      (node (ref "L2") (pin "2") (pinfunction "2_2") (pintype "passive"))
    )
    (net (code "44") (name "P5V0A") (class "Default")
      (node (ref "C119") (pin "1") (pinfunction "1_1") (pintype "passive"))
      (node (ref "C120") (pin "1") (pinfunction "1_1") (pintype "passive"))
      (node (ref "C165") (pin "2") (pinfunction "2_2") (pintype "passive"))
      (node (ref "C77") (pin "2") (pinfunction "2_2") (pintype "passive"))
      (node (ref "C79") (pin "2") (pinfunction "2_2") (pintype "passive"))
      (node (ref "IC11") (pin "10") (pinfunction "BIAS_10") (pintype "input"))
      (node (ref "IC11") (pin "11") (pinfunction "EN_11") (pintype "input"))
      (node (ref "IC16") (pin "10") (pinfunction "OUT_10") (pintype "output"))
      (node (ref "IC16") (pin "9") (pinfunction "OUTS_9") (pintype "output"))
      (node (ref "IC7") (pin "10") (pinfunction "BIAS_10") (pintype "input"))
      (node (ref "IC7") (pin "11") (pinfunction "EN_11") (pintype "input"))
      (node (ref "R110") (pin "2") (pinfunction "2_2") (pintype "passive"))
      (node (ref "R139") (pin "2") (pinfunction "2_2") (pintype "passive"))
      (node (ref "TP16") (pin "1") (pinfunction "1_1") (pintype "bidirectional"))
    )
    (net (code "45") (name "P5V5") (class "Default")
      (node (ref "C152") (pin "2") (pinfunction "2_2") (pintype "passive"))
      (node (ref "C153") (pin "2") (pinfunction "2_2") (pintype "passive"))
      (node (ref "C154") (pin "2") (pinfunction "2_2") (pintype "passive"))
      (node (ref "IC19") (pin "6") (pinfunction "VOS_6") (pintype "input"))
      (node (ref "L4") (pin "2") (pinfunction "2_2") (pintype "passive"))
      (node (ref "L5") (pin "1") (pinfunction "1_1") (pintype "passive"))
      (node (ref "R135") (pin "2") (pinfunction "2_2") (pintype "passive"))
    )
    (net (code "46") (name "P5V5A") (class "Default")
      (node (ref "C117") (pin "1") (pinfunction "1_1") (pintype "passive"))
      (node (ref "C156") (pin "1") (pinfunction "1_1") (pintype "passive"))
      (node (ref "C183") (pin "2") (pinfunction "2_2") (pintype "passive"))
      (node (ref "IC16") (pin "1") (pinfunction "IN_1") (pintype "input"))
      (node (ref "IC16") (pin "2") (pinfunction "IN_2") (pintype "input"))
      (node (ref "IC16") (pin "3") (pinfunction "EN/UV_3") (pintype "input"))
      (node (ref "L5") (pin "2") (pinfunction "2_2") (pintype "passive"))
    )
    (net (code "47") (name "P7V0A") (class "Default")
      (node (ref "C147") (pin "2") (pinfunction "2_2") (pintype "passive"))
      (node (ref "C149") (pin "1") (pinfunction "1_1") (pintype "passive"))
      (node (ref "C150") (pin "1") (pinfunction "1_1") (pintype "passive"))
      (node (ref "IC18") (pin "10") (pinfunction "OUT_10") (pintype "output"))
      (node (ref "IC18") (pin "9") (pinfunction "OUTS_9") (pintype "output"))
      (node (ref "R109") (pin "2") (pinfunction "2_2") (pintype "passive"))
      (node (ref "R133") (pin "2") (pinfunction "2_2") (pintype "passive"))
      (node (ref "TP17") (pin "1") (pinfunction "1_1") (pintype "bidirectional"))
    )
    (net (code "48") (name "P7V5") (class "Default")
      (node (ref "C126") (pin "2") (pinfunction "2_2") (pintype "passive"))
      (node (ref "C127") (pin "1") (pinfunction "1_1") (pintype "passive"))
      (node (ref "C148") (pin "1") (pinfunction "1_1") (pintype "passive"))
      (node (ref "IC18") (pin "1") (pinfunction "IN_1") (pintype "input"))
      (node (ref "IC18") (pin "2") (pinfunction "IN_2") (pintype "input"))
      (node (ref "IC18") (pin "3") (pinfunction "EN/UV_3") (pintype "input"))
      (node (ref "L15") (pin "2") (pinfunction "2_2") (pintype "passive"))
      (node (ref "R53") (pin "2") (pinfunction "2_2") (pintype "passive"))
    )
    (net (code "49") (name "P12V0") (class "Default")
      (node (ref "C157") (pin "2") (pinfunction "2_2") (pintype "passive"))
      (node (ref "C158") (pin "2") (pinfunction "2_2") (pintype "passive"))
      (node (ref "C64") (pin "2") (pinfunction "2_2") (pintype "passive"))
      (node (ref "C70") (pin "2") (pinfunction "2_2") (pintype "passive"))
      (node (ref "IC15") (pin "A2") (pinfunction "VIN_1_A2") (pintype "power_in"))
      (node (ref "IC15") (pin "B3") (pinfunction "VIN_2_B3") (pintype "power_in"))
      (node (ref "IC15") (pin "D3") (pinfunction "VIN_3_D3") (pintype "power_in"))
      (node (ref "IC15") (pin "E2") (pinfunction "VIN_4_E2") (pintype "power_in"))
      (node (ref "IC19") (pin "1") (pinfunction "VIN_1") (pintype "input"))
      (node (ref "IC19") (pin "8") (pinfunction "EN_8") (pintype "input"))
      (node (ref "R134") (pin "2") (pinfunction "2_2") (pintype "passive"))
      (node (ref "R33") (pin "1") (pinfunction "1_1") (pintype "passive"))
      (node (ref "TP18") (pin "1") (pinfunction "1_1") (pintype "bidirectional"))
    )
    (net (code "50") (name "unconnected-(IC7-NC-Pad2)") (class "Default")
      (node (ref "IC7") (pin "2") (pinfunction "NC_2") (pintype "passive+no_connect"))
    )
    (net (code "51") (name "unconnected-(IC7-NC-Pad3)") (class "Default")
      (node (ref "IC7") (pin "3") (pinfunction "NC_3") (pintype "passive+no_connect"))
    )
    (net (code "52") (name "unconnected-(IC7-NC-Pad4)") (class "Default")
      (node (ref "IC7") (pin "4") (pinfunction "NC_4") (pintype "passive+no_connect"))
    )
    (net (code "53") (name "unconnected-(IC7-NC-Pad13)") (class "Default")
      (node (ref "IC7") (pin "13") (pinfunction "NC_13") (pintype "passive+no_connect"))
    )
    (net (code "54") (name "unconnected-(IC7-NC-Pad14)") (class "Default")
      (node (ref "IC7") (pin "14") (pinfunction "NC_14") (pintype "passive+no_connect"))
    )
    (net (code "55") (name "unconnected-(IC7-NC-Pad17)") (class "Default")
      (node (ref "IC7") (pin "17") (pinfunction "NC_17") (pintype "passive+no_connect"))
    )
    (net (code "56") (name "unconnected-(IC7-SS-Pad15)") (class "Default")
      (node (ref "IC7") (pin "15") (pinfunction "SS_15") (pintype "output+no_connect"))
    )
    (net (code "57") (name "unconnected-(IC11-NC-Pad2)") (class "Default")
      (node (ref "IC11") (pin "2") (pinfunction "NC_2") (pintype "passive+no_connect"))
    )
    (net (code "58") (name "unconnected-(IC11-NC-Pad3)") (class "Default")
      (node (ref "IC11") (pin "3") (pinfunction "NC_3") (pintype "passive+no_connect"))
    )
    (net (code "59") (name "unconnected-(IC11-NC-Pad4)") (class "Default")
      (node (ref "IC11") (pin "4") (pinfunction "NC_4") (pintype "passive+no_connect"))
    )
    (net (code "60") (name "unconnected-(IC11-NC-Pad13)") (class "Default")
      (node (ref "IC11") (pin "13") (pinfunction "NC_13") (pintype "passive+no_connect"))
    )
    (net (code "61") (name "unconnected-(IC11-NC-Pad14)") (class "Default")
      (node (ref "IC11") (pin "14") (pinfunction "NC_14") (pintype "passive+no_connect"))
    )
    (net (code "62") (name "unconnected-(IC11-NC-Pad17)") (class "Default")
      (node (ref "IC11") (pin "17") (pinfunction "NC_17") (pintype "passive+no_connect"))
    )
    (net (code "63") (name "unconnected-(IC11-SS-Pad15)") (class "Default")
      (node (ref "IC11") (pin "15") (pinfunction "SS_15") (pintype "output+no_connect"))
    )
  )
)
